# light.net
KiCad netlist of a schematic drawn in Altium Designer
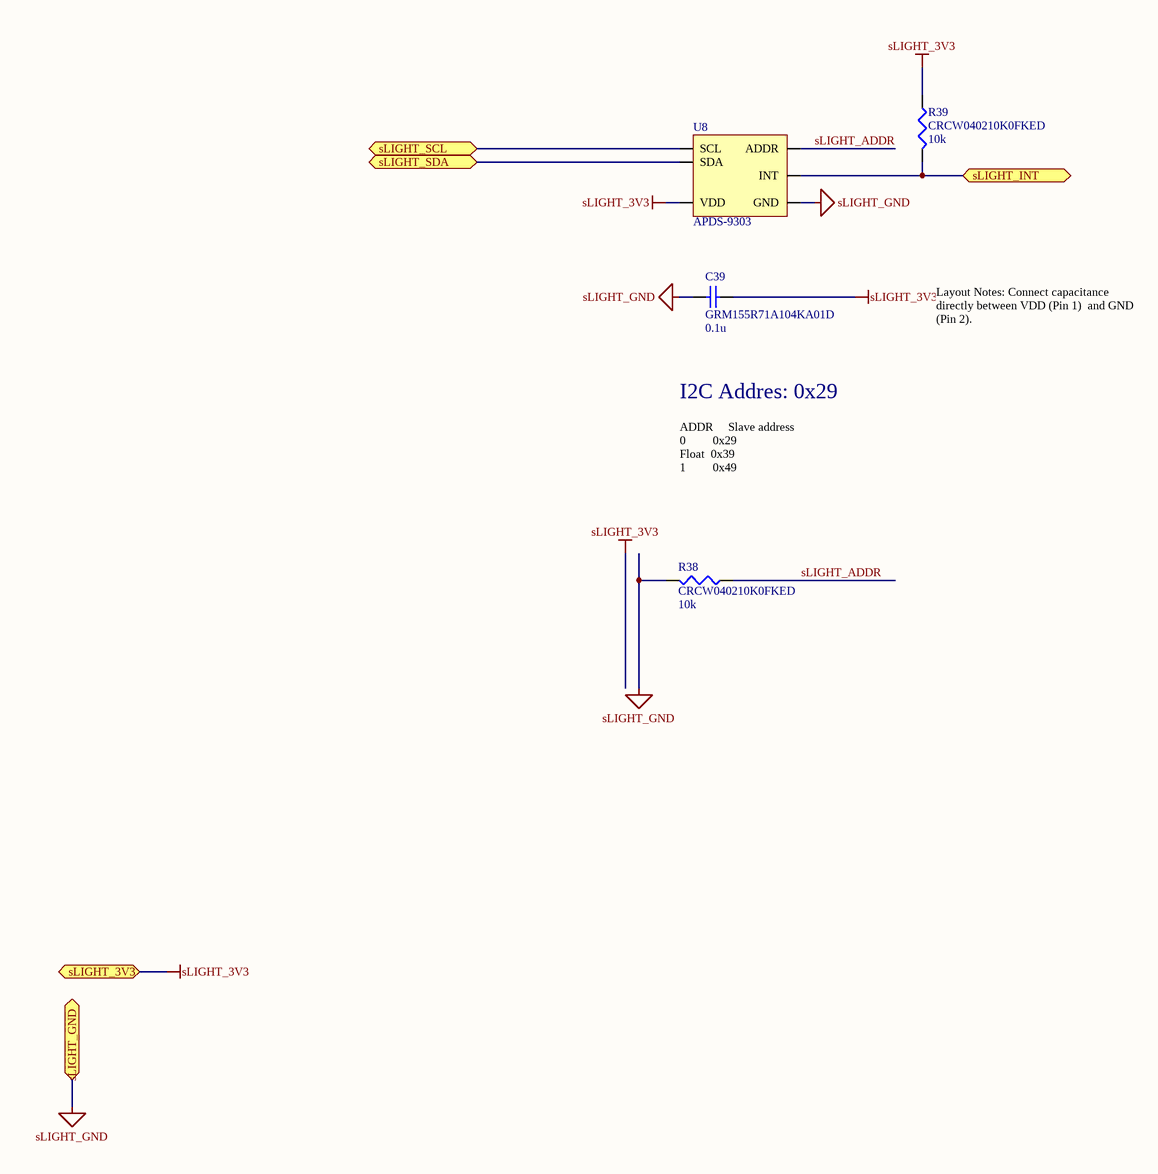
[diagram p0: _light.SchDoc]

(export (version "E")
  (design (tool "Eeschema 10.0.6"))
  (components
    (comp (ref "C39")
      (value "GRM155R71A104KA01D")
      (footprint "0402")
      (description "-55-125C, 1005, 10V, X7R, ±10%")
      (fields (field (name "ALTIUM_VALUE") "0.1u"))
      (libsource (lib "standard_capacitors") (part "GRM155R71AxxxKdddd"))
    )
    (comp (ref "R38")
      (value "CRCW040210K0FKED")
      (footprint "0402")
      (description "0.125W, -55-155C, 1005, 50V, ±1%")
      (fields (field (name "ALTIUM_VALUE") "10k"))
      (libsource (lib "standard_resistors") (part "CRCW0402xxxxFKED"))
    )
    (comp (ref "R39")
      (value "CRCW040210K0FKED")
      (footprint "0402")
      (description "0.125W, -55-155C, 1005, 50V, ±1%")
      (fields (field (name "ALTIUM_VALUE") "10k"))
      (libsource (lib "standard_resistors") (part "CRCW0402xxxxFKED"))
    )
    (comp (ref "U8") (value "APDS-9303") (footprint "APDS-9303") (libsource (lib "avago") (part "APDS-9303")))
  )
  (nets
    (net (code "1") (name "/sLIGHT_ADDR") (class "Default")
      (node (ref "R38") (pin "1") (pinfunction "1_1") (pintype "passive"))
      (node (ref "U8") (pin "3") (pinfunction "ADDR_3") (pintype "passive"))
    )
    (net (code "2") (name "/sLIGHT_INT") (class "Default")
      (node (ref "R39") (pin "2") (pinfunction "2_2") (pintype "passive"))
      (node (ref "U8") (pin "6") (pinfunction "INT_6") (pintype "passive"))
    )
    (net (code "3") (name "/sLIGHT_SCL") (class "Default")
      (node (ref "U8") (pin "4") (pinfunction "SCL_4") (pintype "passive"))
    )
    (net (code "4") (name "/sLIGHT_SDA") (class "Default")
      (node (ref "U8") (pin "5") (pinfunction "SDA_5") (pintype "passive"))
    )
    (net (code "5") (name "sLIGHT_3V3") (class "Default")
      (node (ref "C39") (pin "2") (pinfunction "2_2") (pintype "passive"))
      (node (ref "R39") (pin "1") (pinfunction "1_1") (pintype "passive"))
      (node (ref "U8") (pin "1") (pinfunction "VDD_1") (pintype "passive"))
    )
    (net (code "6") (name "sLIGHT_GND") (class "Default")
      (node (ref "C39") (pin "1") (pinfunction "1_1") (pintype "passive"))
      (node (ref "R38") (pin "2") (pinfunction "2_2") (pintype "passive"))
      (node (ref "U8") (pin "2") (pinfunction "GND_2") (pintype "passive"))
    )
  )
)
